# CH32V203F8U6-R0.net
KiCad netlist of a schematic drawn in Altium Designer
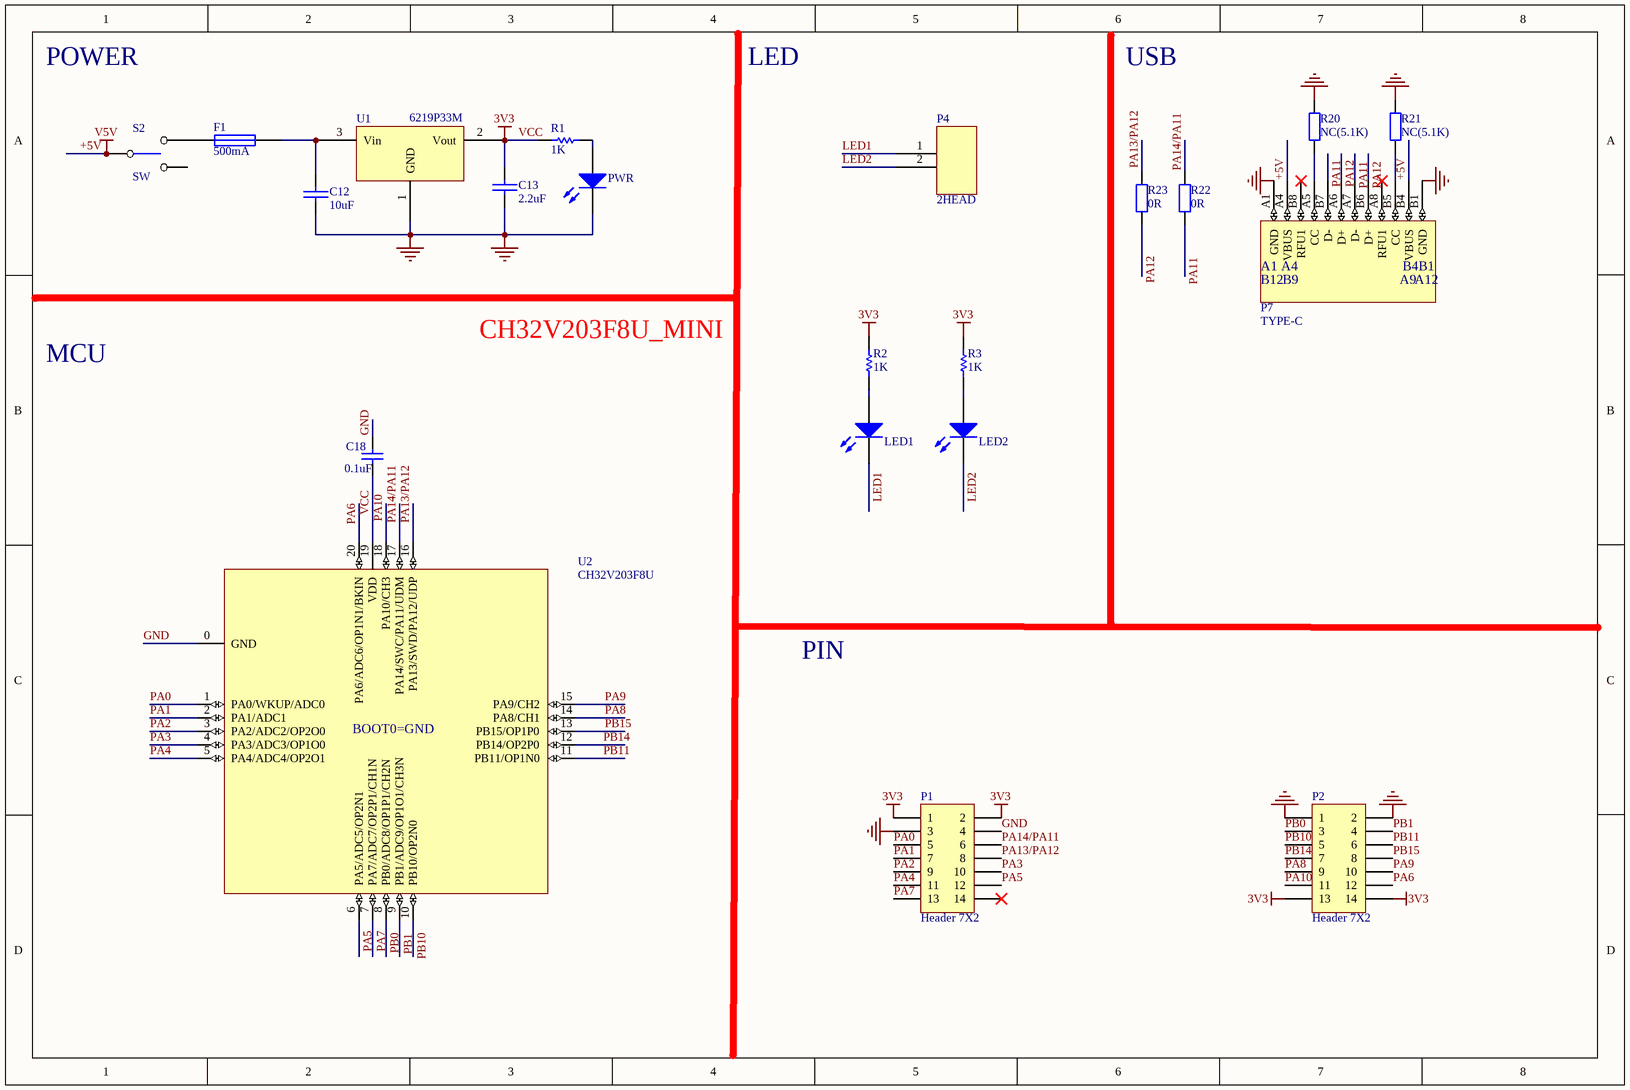
[diagram p0: CH32V203F8U6-R0.SchDoc]

(export (version "E")
  (design (tool "Eeschema 10.0.6"))
  (components
    (comp (ref "C12")
      (value "10uF")
      (footprint "3216_C")
      (description "Capacitor")
      (libsource (lib "wch_sch_others") (part "CAP"))
    )
    (comp (ref "C13")
      (value "2.2uF")
      (footprint "0603_C")
      (description "Capacitor")
      (libsource (lib "wch_sch_others") (part "CAP"))
    )
    (comp (ref "C18")
      (value "0.1uF")
      (footprint "0603_C")
      (description "Capacitor")
      (fields (field (name "PUBLISHER") "Altium Limited"))
      (libsource (lib "*") (part "Cap"))
    )
    (comp (ref "F1")
      (value "500mA")
      (footprint "0603")
      (description "Fuse")
      (libsource (lib "*") (part "FUSE1"))
    )
    (comp (ref "LED1")
      (value "LED1   blue")
      (footprint "0603+")
      (description "Typical INFRARED GaAs LED")
      (fields (field (name "PUBLISHER") "Altium Limited"))
      (libsource (lib "") (part "LED0_1"))
    )
    (comp (ref "LED2")
      (value "LED2  blue")
      (footprint "0603+")
      (description "Typical INFRARED GaAs LED")
      (fields (field (name "PUBLISHER") "Altium Limited"))
      (libsource (lib "") (part "LED0_1"))
    )
    (comp (ref "P1")
      (value "Header 7X2")
      (footprint "IDC14-2.54mm")
      (description "Header, 7-Pin, Dual row")
      (fields (field (name "PUBLISHER") "Altium Limited"))
      (libsource (lib "Miscellaneous Connectors") (part "Header 7X2"))
    )
    (comp (ref "P2")
      (value "Header 7X2")
      (footprint "IDC14-2.54mm")
      (description "Header, 7-Pin, Dual row")
      (fields (field (name "PUBLISHER") "Altium Limited"))
      (libsource (lib "Miscellaneous Connectors") (part "Header 7X2"))
    )
    (comp (ref "P4") (value "2HEAD") (footprint "SIP2-2.54mm") (libsource (lib "*") (part "2HEAD")))
    (comp (ref "P7")
      (value "TYPE-C")
      (footprint "TYPE-C-Receptacle-2.0")
      (libsource (lib "*") (part "TYPE-C1"))
    )
    (comp (ref "PWR")
      (value "POWER  red")
      (footprint "0603+")
      (description "Typical INFRARED GaAs LED")
      (fields (field (name "PUBLISHER") "Altium Limited"))
      (libsource (lib "*") (part "LED0"))
    )
    (comp (ref "R1")
      (value "1K")
      (footprint "0603")
      (description "Semiconductor Resistor")
      (fields (field (name "PUBLISHER") "Altium Limited"))
      (libsource (lib "*") (part "Res Semi"))
    )
    (comp (ref "R2")
      (value "1K")
      (footprint "0603")
      (description "Semiconductor Resistor")
      (fields (field (name "PUBLISHER") "Altium Limited"))
      (libsource (lib "*") (part "Res Semi"))
    )
    (comp (ref "R3")
      (value "1K")
      (footprint "0603")
      (description "Semiconductor Resistor")
      (fields (field (name "PUBLISHER") "Altium Limited"))
      (libsource (lib "*") (part "Res Semi"))
    )
    (comp (ref "R20")
      (value "NC(5.1K)")
      (footprint "0603")
      (description "Resistor")
      (libsource (lib "Miscellaneous Devices") (part "Res2"))
    )
    (comp (ref "R21")
      (value "NC(5.1K)")
      (footprint "0603")
      (description "Resistor")
      (libsource (lib "Miscellaneous Devices") (part "Res2"))
    )
    (comp (ref "R22")
      (value "0R")
      (footprint "0603")
      (description "Resistor")
      (libsource (lib "Miscellaneous Devices") (part "Res2"))
    )
    (comp (ref "R23")
      (value "0R")
      (footprint "0603")
      (description "Resistor")
      (libsource (lib "Miscellaneous Devices") (part "Res2"))
    )
    (comp (ref "S2") (value "SW") (footprint "SW1") (libsource (lib "*") (part "SW")))
    (comp (ref "U1")
      (value "6219P33M")
      (footprint "SOT-23")
      (libsource (lib "wch_sch_others") (part "6219P33M"))
    )
    (comp (ref "U2")
      (value "CH32V203F8U")
      (footprint "QFN20_3x3")
      (description "RISC-V LMD-MCU, 144MHz, for motor & wireless charging")
      (libsource (lib "CHXXX") (part "CH32V203F8U"))
    )
  )
  (nets
    (net (code "1") (name "/LED1") (class "Default")
      (node (ref "LED1") (pin "2") (pinfunction "K_2") (pintype "passive"))
      (node (ref "P4") (pin "1") (pintype "passive"))
    )
    (net (code "2") (name "/LED2") (class "Default")
      (node (ref "LED2") (pin "2") (pinfunction "K_2") (pintype "passive"))
      (node (ref "P4") (pin "2") (pintype "passive"))
    )
    (net (code "3") (name "/PA0") (class "Default")
      (node (ref "P1") (pin "5") (pinfunction "5_5") (pintype "passive"))
      (node (ref "U2") (pin "1") (pinfunction "PA0/WKUP/ADC0_1") (pintype "bidirectional"))
    )
    (net (code "4") (name "/PA1") (class "Default")
      (node (ref "P1") (pin "7") (pinfunction "7_7") (pintype "passive"))
      (node (ref "U2") (pin "2") (pinfunction "PA1/ADC1_2") (pintype "bidirectional"))
    )
    (net (code "5") (name "/PA2") (class "Default")
      (node (ref "P1") (pin "9") (pinfunction "9_9") (pintype "passive"))
      (node (ref "U2") (pin "3") (pinfunction "PA2/ADC2/OP2O0_3") (pintype "bidirectional"))
    )
    (net (code "6") (name "/PA3") (class "Default")
      (node (ref "P1") (pin "10") (pinfunction "10_10") (pintype "passive"))
      (node (ref "U2") (pin "4") (pinfunction "PA3/ADC3/OP1O0_4") (pintype "bidirectional"))
    )
    (net (code "7") (name "/PA4") (class "Default")
      (node (ref "P1") (pin "11") (pinfunction "11_11") (pintype "passive"))
      (node (ref "U2") (pin "5") (pinfunction "PA4/ADC4/OP2O1_5") (pintype "bidirectional"))
    )
    (net (code "8") (name "/PA5") (class "Default")
      (node (ref "P1") (pin "12") (pinfunction "12_12") (pintype "passive"))
      (node (ref "U2") (pin "6") (pinfunction "PA5/ADC5/OP2N1_6") (pintype "bidirectional"))
    )
    (net (code "9") (name "/PA6") (class "Default")
      (node (ref "P2") (pin "12") (pinfunction "12_12") (pintype "passive"))
      (node (ref "U2") (pin "20") (pinfunction "PA6/ADC6/OP1N1/BKIN_20") (pintype "bidirectional"))
    )
    (net (code "10") (name "/PA7") (class "Default")
      (node (ref "P1") (pin "13") (pinfunction "13_13") (pintype "passive"))
      (node (ref "U2") (pin "7") (pinfunction "PA7/ADC7/OP2P1/CH1N_7") (pintype "bidirectional"))
    )
    (net (code "11") (name "/PA8") (class "Default")
      (node (ref "P2") (pin "9") (pinfunction "9_9") (pintype "passive"))
      (node (ref "U2") (pin "14") (pinfunction "PA8/CH1_14") (pintype "bidirectional"))
    )
    (net (code "12") (name "/PA9") (class "Default")
      (node (ref "P2") (pin "10") (pinfunction "10_10") (pintype "passive"))
      (node (ref "U2") (pin "15") (pinfunction "PA9/CH2_15") (pintype "bidirectional"))
    )
    (net (code "13") (name "/PA10") (class "Default")
      (node (ref "P2") (pin "11") (pinfunction "11_11") (pintype "passive"))
      (node (ref "U2") (pin "18") (pinfunction "PA10/CH3_18") (pintype "bidirectional"))
    )
    (net (code "14") (name "/PA11") (class "Default")
      (node (ref "P7") (pin "A7") (pinfunction "D-_A7") (pintype "bidirectional"))
      (node (ref "P7") (pin "B7") (pinfunction "D-_B7") (pintype "bidirectional"))
      (node (ref "R22") (pin "1") (pinfunction "1_1") (pintype "passive"))
    )
    (net (code "15") (name "/PA12") (class "Default")
      (node (ref "P7") (pin "A6") (pinfunction "D+_A6") (pintype "bidirectional"))
      (node (ref "P7") (pin "B6") (pinfunction "D+_B6") (pintype "bidirectional"))
      (node (ref "R23") (pin "1") (pinfunction "1_1") (pintype "passive"))
    )
    (net (code "16") (name "/PA13{slash}PA12") (class "Default")
      (node (ref "P1") (pin "8") (pinfunction "8_8") (pintype "passive"))
      (node (ref "R23") (pin "2") (pinfunction "2_2") (pintype "passive"))
      (node (ref "U2") (pin "16") (pinfunction "PA13/SWD/PA12/UDP_16") (pintype "bidirectional"))
    )
    (net (code "17") (name "/PA14{slash}PA11") (class "Default")
      (node (ref "P1") (pin "6") (pinfunction "6_6") (pintype "passive"))
      (node (ref "R22") (pin "2") (pinfunction "2_2") (pintype "passive"))
      (node (ref "U2") (pin "17") (pinfunction "PA14/SWC/PA11/UDM_17") (pintype "bidirectional"))
    )
    (net (code "18") (name "/PB0") (class "Default")
      (node (ref "P2") (pin "3") (pinfunction "3_3") (pintype "passive"))
      (node (ref "U2") (pin "8") (pinfunction "PB0/ADC8/OP1P1/CH2N_8") (pintype "bidirectional"))
    )
    (net (code "19") (name "/PB1") (class "Default")
      (node (ref "P2") (pin "4") (pinfunction "4_4") (pintype "passive"))
      (node (ref "U2") (pin "9") (pinfunction "PB1/ADC9/OP1O1/CH3N_9") (pintype "bidirectional"))
    )
    (net (code "20") (name "/PB10") (class "Default")
      (node (ref "P2") (pin "5") (pinfunction "5_5") (pintype "passive"))
      (node (ref "U2") (pin "10") (pinfunction "PB10/OP2N0_10") (pintype "bidirectional"))
    )
    (net (code "21") (name "/PB11") (class "Default")
      (node (ref "P2") (pin "6") (pinfunction "6_6") (pintype "passive"))
      (node (ref "U2") (pin "11") (pinfunction "PB11/OP1N0_11") (pintype "bidirectional"))
    )
    (net (code "22") (name "/PB14") (class "Default")
      (node (ref "P2") (pin "7") (pinfunction "7_7") (pintype "passive"))
      (node (ref "U2") (pin "12") (pinfunction "PB14/OP2P0_12") (pintype "bidirectional"))
    )
    (net (code "23") (name "/PB15") (class "Default")
      (node (ref "P2") (pin "8") (pinfunction "8_8") (pintype "passive"))
      (node (ref "U2") (pin "13") (pinfunction "PB15/OP1P0_13") (pintype "bidirectional"))
    )
    (net (code "24") (name "3V3") (class "Default")
      (node (ref "C13") (pin "2") (pinfunction "2_2") (pintype "passive"))
      (node (ref "C18") (pin "1") (pinfunction "1_1") (pintype "passive"))
      (node (ref "P1") (pin "1") (pinfunction "1_1") (pintype "passive"))
      (node (ref "P1") (pin "2") (pinfunction "2_2") (pintype "passive"))
      (node (ref "P2") (pin "13") (pinfunction "13_13") (pintype "passive"))
      (node (ref "P2") (pin "14") (pinfunction "14_14") (pintype "passive"))
      (node (ref "R1") (pin "2") (pinfunction "2_2") (pintype "passive"))
      (node (ref "R2") (pin "1") (pinfunction "1_1") (pintype "passive"))
      (node (ref "R3") (pin "1") (pinfunction "1_1") (pintype "passive"))
      (node (ref "U1") (pin "2") (pinfunction "Vout_2") (pintype "passive"))
      (node (ref "U2") (pin "19") (pinfunction "VDD_19") (pintype "power_in"))
    )
    (net (code "25") (name "GND") (class "Default")
      (node (ref "C12") (pin "2") (pinfunction "2_2") (pintype "passive"))
      (node (ref "C13") (pin "1") (pinfunction "1_1") (pintype "passive"))
      (node (ref "C18") (pin "2") (pinfunction "2_2") (pintype "passive"))
      (node (ref "P1") (pin "3") (pinfunction "3_3") (pintype "passive"))
      (node (ref "P1") (pin "4") (pinfunction "4_4") (pintype "passive"))
      (node (ref "P2") (pin "1") (pinfunction "1_1") (pintype "passive"))
      (node (ref "P2") (pin "2") (pinfunction "2_2") (pintype "passive"))
      (node (ref "P7") (pin "A1") (pinfunction "GND_A1") (pintype "bidirectional"))
      (node (ref "P7") (pin "B1") (pinfunction "GND_B1") (pintype "bidirectional"))
      (node (ref "PWR") (pin "2") (pinfunction "K_2") (pintype "passive"))
      (node (ref "R20") (pin "2") (pinfunction "2_2") (pintype "passive"))
      (node (ref "R21") (pin "2") (pinfunction "2_2") (pintype "passive"))
      (node (ref "U1") (pin "1") (pinfunction "GND_1") (pintype "passive"))
      (node (ref "U2") (pin "0") (pinfunction "GND_0") (pintype "power_in"))
    )
    (net (code "26") (name "Net-(F1-Pad1)") (class "Default")
      (node (ref "F1") (pin "1") (pinfunction "1_1") (pintype "passive"))
      (node (ref "S2") (pin "3") (pinfunction "3_3") (pintype "passive"))
    )
    (net (code "27") (name "Net-(LED1-A)") (class "Default")
      (node (ref "LED1") (pin "1") (pinfunction "A_1") (pintype "passive"))
      (node (ref "R2") (pin "2") (pinfunction "2_2") (pintype "passive"))
    )
    (net (code "28") (name "Net-(LED2-A)") (class "Default")
      (node (ref "LED2") (pin "1") (pinfunction "A_1") (pintype "passive"))
      (node (ref "R3") (pin "2") (pinfunction "2_2") (pintype "passive"))
    )
    (net (code "29") (name "Net-(P7-CC-PadA5)") (class "Default")
      (node (ref "P7") (pin "A5") (pinfunction "CC_A5") (pintype "bidirectional"))
      (node (ref "R20") (pin "1") (pinfunction "1_1") (pintype "passive"))
    )
    (net (code "30") (name "Net-(P7-CC-PadB5)") (class "Default")
      (node (ref "P7") (pin "B5") (pinfunction "CC_B5") (pintype "bidirectional"))
      (node (ref "R21") (pin "1") (pinfunction "1_1") (pintype "passive"))
    )
    (net (code "31") (name "Net-(PWR-A)") (class "Default")
      (node (ref "PWR") (pin "1") (pinfunction "A_1") (pintype "passive"))
      (node (ref "R1") (pin "1") (pinfunction "1_1") (pintype "passive"))
    )
    (net (code "32") (name "Net-(U1-Vin)") (class "Default")
      (node (ref "C12") (pin "1") (pinfunction "1_1") (pintype "passive"))
      (node (ref "F1") (pin "2") (pinfunction "2_2") (pintype "passive"))
      (node (ref "U1") (pin "3") (pinfunction "Vin_3") (pintype "passive"))
    )
    (net (code "33") (name "V5V") (class "Default")
      (node (ref "P7") (pin "A4") (pinfunction "VBUS_A4") (pintype "bidirectional"))
      (node (ref "P7") (pin "B4") (pinfunction "VBUS_B4") (pintype "bidirectional"))
      (node (ref "S2") (pin "1") (pinfunction "1_1") (pintype "passive"))
    )
    (net (code "34") (name "unconnected-(P1-Pad14)") (class "Default")
      (node (ref "P1") (pin "14") (pinfunction "14_14") (pintype "passive+no_connect"))
    )
    (net (code "35") (name "unconnected-(P7-RFU1-PadA8)") (class "Default")
      (node (ref "P7") (pin "A8") (pinfunction "RFU1_A8") (pintype "bidirectional+no_connect"))
    )
    (net (code "36") (name "unconnected-(P7-RFU1-PadB8)") (class "Default")
      (node (ref "P7") (pin "B8") (pinfunction "RFU1_B8") (pintype "bidirectional+no_connect"))
    )
    (net (code "37") (name "unconnected-(S2-Pad2)") (class "Default")
      (node (ref "S2") (pin "2") (pinfunction "2_2") (pintype "passive"))
    )
  )
)
